# nrf24_fab.net
KiCad netlist of a schematic drawn in EAGLE
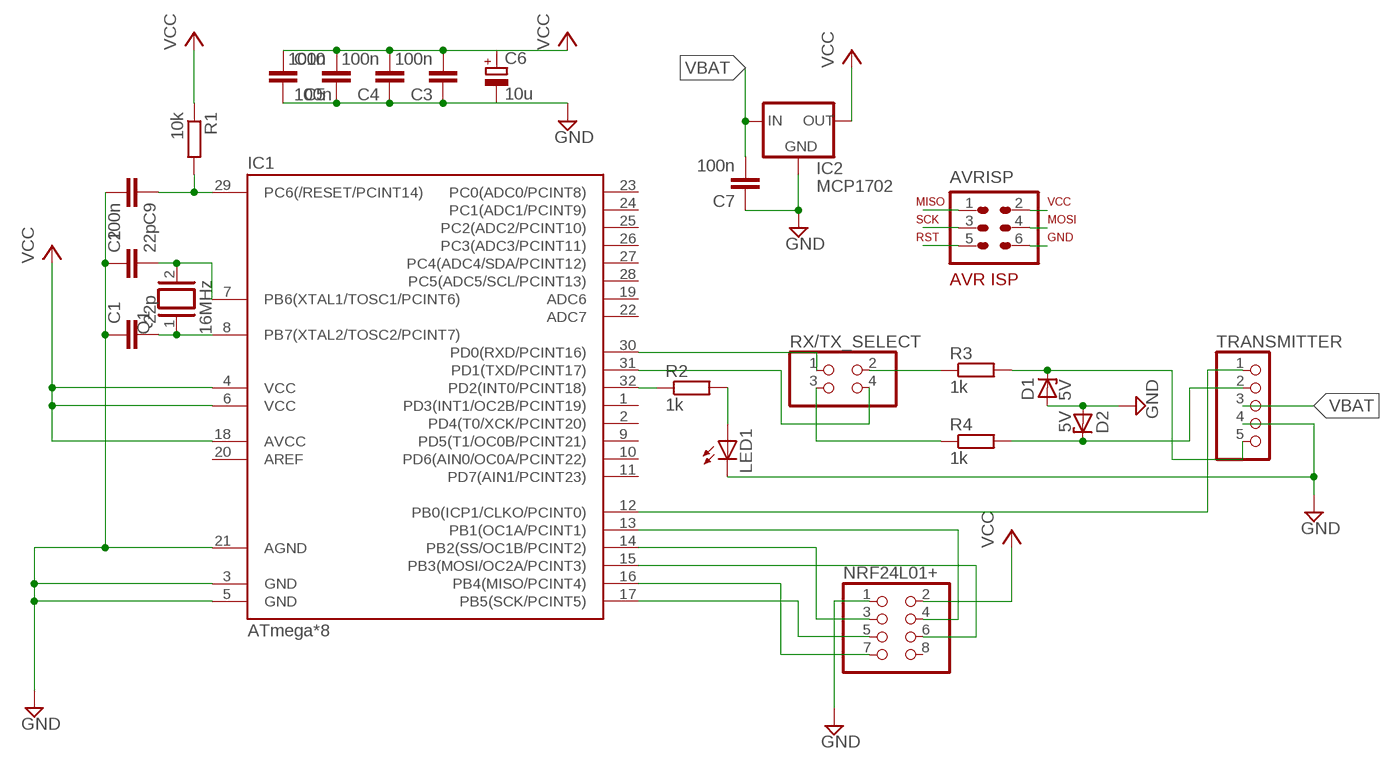
[diagram p0: schematic, sheet 1]

(export (version "E")
  (design (tool "Eeschema 10.0.6"))
  (components
    (comp (ref "AVRISP")
      (value "AVR-ISP-6VERT")
      (footprint "eagle-import:AVR-ISP-6")
      (libsource (lib "eagle-import") (part "AVR-ISP-6VERT"))
    )
    (comp (ref "C1")
      (value "22p")
      (footprint "eagle-import:C0805")
      (libsource (lib "eagle-import") (part "C-EUC0805"))
    )
    (comp (ref "C2")
      (value "22p")
      (footprint "eagle-import:C0805")
      (libsource (lib "eagle-import") (part "C-EUC0805"))
    )
    (comp (ref "C3")
      (value "100n")
      (footprint "eagle-import:C0805")
      (libsource (lib "eagle-import") (part "C-EUC0805"))
    )
    (comp (ref "C4")
      (value "100n")
      (footprint "eagle-import:C0805")
      (libsource (lib "eagle-import") (part "C-EUC0805"))
    )
    (comp (ref "C5")
      (value "100n")
      (footprint "eagle-import:C0805")
      (libsource (lib "eagle-import") (part "C-EUC0805"))
    )
    (comp (ref "C6")
      (value "10u")
      (footprint "eagle-import:E2,5-6")
      (libsource (lib "eagle-import") (part "CPOL-EUE2.5-6"))
    )
    (comp (ref "C7")
      (value "100n")
      (footprint "eagle-import:C0805")
      (libsource (lib "eagle-import") (part "C-EUC0805"))
    )
    (comp (ref "C9")
      (value "100n")
      (footprint "eagle-import:C0805")
      (libsource (lib "eagle-import") (part "C-EUC0805"))
    )
    (comp (ref "C10")
      (value "100n")
      (footprint "eagle-import:C0805")
      (libsource (lib "eagle-import") (part "C-EUC0805"))
    )
    (comp (ref "D1")
      (value "5V")
      (footprint "eagle-import:SOD80C")
      (libsource (lib "eagle-import") (part "ZENER-DIODESOD80C"))
    )
    (comp (ref "D2")
      (value "5V")
      (footprint "eagle-import:SOD80C")
      (libsource (lib "eagle-import") (part "ZENER-DIODESOD80C"))
    )
    (comp (ref "IC1")
      (value "ATmega*8")
      (footprint "eagle-import:TQFP32-08")
      (libsource (lib "eagle-import") (part "MEGA48/88/168-AU"))
    )
    (comp (ref "IC2")
      (value "MCP1702")
      (footprint "eagle-import:TO-92")
      (libsource (lib "eagle-import") (part "MCP1702"))
    )
    (comp (ref "LED1")
      (value "LEDSMT1206")
      (footprint "eagle-import:1206")
      (libsource (lib "eagle-import") (part "LEDSMT1206"))
    )
    (comp (ref "NRF24L01+")
      (value "PINHD-2X4")
      (footprint "eagle-import:2X04")
      (libsource (lib "eagle-import") (part "PINHD-2X4"))
    )
    (comp (ref "Q1")
      (value "16MHz")
      (footprint "eagle-import:QS")
      (libsource (lib "eagle-import") (part "XTAL/S"))
    )
    (comp (ref "R1")
      (value "10k")
      (footprint "eagle-import:M0805")
      (libsource (lib "eagle-import") (part "R-EU_M0805"))
    )
    (comp (ref "R2")
      (value "1k")
      (footprint "eagle-import:M0805")
      (libsource (lib "eagle-import") (part "R-EU_M0805"))
    )
    (comp (ref "R3")
      (value "1k")
      (footprint "eagle-import:M0805")
      (libsource (lib "eagle-import") (part "R-EU_M0805"))
    )
    (comp (ref "R4")
      (value "1k")
      (footprint "eagle-import:M0805")
      (libsource (lib "eagle-import") (part "R-EU_M0805"))
    )
    (comp (ref "RX/TX_SELECT")
      (value "PINHD-2X2")
      (footprint "eagle-import:2X02")
      (libsource (lib "eagle-import") (part "PINHD-2X2"))
    )
    (comp (ref "TRANSMITTER")
      (value "PINHD-1X5")
      (footprint "eagle-import:1X05")
      (libsource (lib "eagle-import") (part "PINHD-1X5"))
    )
  )
  (nets
    (net (code "1") (name "/MISO") (class "Default")
      (node (ref "AVRISP") (pin "1") (pinfunction "1_1") (pintype "passive"))
      (node (ref "IC1") (pin "16") (pinfunction "PB4(MISO/PCINT4)_16") (pintype "bidirectional"))
      (node (ref "NRF24L01+") (pin "7") (pinfunction "7_7") (pintype "passive"))
    )
    (net (code "2") (name "/MOSI") (class "Default")
      (node (ref "AVRISP") (pin "4") (pinfunction "4_4") (pintype "passive"))
      (node (ref "IC1") (pin "15") (pinfunction "PB3(MOSI/OC2A/PCINT3)_15") (pintype "bidirectional"))
      (node (ref "NRF24L01+") (pin "6") (pinfunction "6_6") (pintype "passive"))
    )
    (net (code "3") (name "/RST") (class "Default")
      (node (ref "AVRISP") (pin "5") (pinfunction "5_5") (pintype "passive"))
      (node (ref "C9") (pin "1") (pinfunction "1_1") (pintype "passive"))
      (node (ref "IC1") (pin "29") (pinfunction "PC6(/RESET/PCINT14)_29") (pintype "bidirectional"))
      (node (ref "R1") (pin "2") (pinfunction "2_2") (pintype "passive"))
    )
    (net (code "4") (name "/SCK") (class "Default")
      (node (ref "AVRISP") (pin "3") (pinfunction "3_3") (pintype "passive"))
      (node (ref "IC1") (pin "17") (pinfunction "PB5(SCK/PCINT5)_17") (pintype "bidirectional"))
      (node (ref "NRF24L01+") (pin "5") (pinfunction "5_5") (pintype "passive"))
    )
    (net (code "5") (name "GND") (class "Default")
      (node (ref "AVRISP") (pin "6") (pinfunction "6_6") (pintype "passive"))
      (node (ref "C1") (pin "1") (pinfunction "1_1") (pintype "passive"))
      (node (ref "C10") (pin "2") (pinfunction "2_2") (pintype "passive"))
      (node (ref "C2") (pin "1") (pinfunction "1_1") (pintype "passive"))
      (node (ref "C3") (pin "1") (pinfunction "1_1") (pintype "passive"))
      (node (ref "C4") (pin "1") (pinfunction "1_1") (pintype "passive"))
      (node (ref "C5") (pin "1") (pinfunction "1_1") (pintype "passive"))
      (node (ref "C6") (pin "-") (pinfunction "-_-") (pintype "passive"))
      (node (ref "C7") (pin "1") (pinfunction "1_1") (pintype "passive"))
      (node (ref "C9") (pin "2") (pinfunction "2_2") (pintype "passive"))
      (node (ref "D1") (pin "A") (pinfunction "A_A") (pintype "passive"))
      (node (ref "D2") (pin "A") (pinfunction "A_A") (pintype "passive"))
      (node (ref "IC1") (pin "21") (pinfunction "AGND_21") (pintype "power_in"))
      (node (ref "IC1") (pin "3") (pinfunction "GND_3") (pintype "power_in"))
      (node (ref "IC1") (pin "5") (pinfunction "GND_5") (pintype "power_in"))
      (node (ref "IC2") (pin "1") (pinfunction "GND_1") (pintype "power_in"))
      (node (ref "LED1") (pin "C") (pinfunction "C_C") (pintype "passive"))
      (node (ref "NRF24L01+") (pin "1") (pinfunction "1_1") (pintype "passive"))
      (node (ref "TRANSMITTER") (pin "4") (pinfunction "4_4") (pintype "passive"))
    )
    (net (code "6") (name "Net-(D1-PadC)") (class "Default")
      (node (ref "D1") (pin "C") (pinfunction "C_C") (pintype "passive"))
      (node (ref "R3") (pin "2") (pinfunction "2_2") (pintype "passive"))
      (node (ref "TRANSMITTER") (pin "5") (pinfunction "5_5") (pintype "passive"))
    )
    (net (code "7") (name "Net-(D2-PadC)") (class "Default")
      (node (ref "D2") (pin "C") (pinfunction "C_C") (pintype "passive"))
      (node (ref "R4") (pin "2") (pinfunction "2_2") (pintype "passive"))
      (node (ref "TRANSMITTER") (pin "2") (pinfunction "2_2") (pintype "passive"))
    )
    (net (code "8") (name "Net-(IC1-PB0(ICP1{slash}CLKO{slash}PCINT0))") (class "Default")
      (node (ref "IC1") (pin "12") (pinfunction "PB0(ICP1/CLKO/PCINT0)_12") (pintype "bidirectional"))
      (node (ref "TRANSMITTER") (pin "1") (pinfunction "1_1") (pintype "passive"))
    )
    (net (code "9") (name "Net-(IC1-PB1(OC1A{slash}PCINT1))") (class "Default")
      (node (ref "IC1") (pin "13") (pinfunction "PB1(OC1A/PCINT1)_13") (pintype "bidirectional"))
      (node (ref "NRF24L01+") (pin "4") (pinfunction "4_4") (pintype "passive"))
    )
    (net (code "10") (name "Net-(IC1-PB2(SS{slash}OC1B{slash}PCINT2))") (class "Default")
      (node (ref "IC1") (pin "14") (pinfunction "PB2(SS/OC1B/PCINT2)_14") (pintype "bidirectional"))
      (node (ref "NRF24L01+") (pin "3") (pinfunction "3_3") (pintype "passive"))
    )
    (net (code "11") (name "Net-(IC1-PB6(XTAL1{slash}TOSC1{slash}PCINT6))") (class "Default")
      (node (ref "C2") (pin "2") (pinfunction "2_2") (pintype "passive"))
      (node (ref "IC1") (pin "7") (pinfunction "PB6(XTAL1/TOSC1/PCINT6)_7") (pintype "bidirectional"))
      (node (ref "Q1") (pin "2") (pinfunction "2_2") (pintype "passive"))
    )
    (net (code "12") (name "Net-(IC1-PB7(XTAL2{slash}TOSC2{slash}PCINT7))") (class "Default")
      (node (ref "C1") (pin "2") (pinfunction "2_2") (pintype "passive"))
      (node (ref "IC1") (pin "8") (pinfunction "PB7(XTAL2/TOSC2/PCINT7)_8") (pintype "bidirectional"))
      (node (ref "Q1") (pin "1") (pinfunction "1_1") (pintype "passive"))
    )
    (net (code "13") (name "Net-(IC1-PD0(RXD{slash}PCINT16))") (class "Default")
      (node (ref "IC1") (pin "30") (pinfunction "PD0(RXD/PCINT16)_30") (pintype "bidirectional"))
      (node (ref "RX/TX_SELECT") (pin "1") (pinfunction "1_1") (pintype "passive"))
    )
    (net (code "14") (name "Net-(IC1-PD1(TXD{slash}PCINT17))") (class "Default")
      (node (ref "IC1") (pin "31") (pinfunction "PD1(TXD/PCINT17)_31") (pintype "bidirectional"))
      (node (ref "RX/TX_SELECT") (pin "4") (pinfunction "4_4") (pintype "passive"))
    )
    (net (code "15") (name "Net-(IC1-PD2(INT0{slash}PCINT18))") (class "Default")
      (node (ref "IC1") (pin "32") (pinfunction "PD2(INT0/PCINT18)_32") (pintype "bidirectional"))
      (node (ref "R2") (pin "1") (pinfunction "1_1") (pintype "passive"))
    )
    (net (code "16") (name "Net-(LED1-PadA)") (class "Default")
      (node (ref "LED1") (pin "A") (pinfunction "A_A") (pintype "passive"))
      (node (ref "R2") (pin "2") (pinfunction "2_2") (pintype "passive"))
    )
    (net (code "17") (name "Net-(R3-Pad1)") (class "Default")
      (node (ref "R3") (pin "1") (pinfunction "1_1") (pintype "passive"))
      (node (ref "RX/TX_SELECT") (pin "2") (pinfunction "2_2") (pintype "passive"))
    )
    (net (code "18") (name "Net-(R4-Pad1)") (class "Default")
      (node (ref "R4") (pin "1") (pinfunction "1_1") (pintype "passive"))
      (node (ref "RX/TX_SELECT") (pin "3") (pinfunction "3_3") (pintype "passive"))
    )
    (net (code "19") (name "VBAT") (class "Default")
      (node (ref "C7") (pin "2") (pinfunction "2_2") (pintype "passive"))
      (node (ref "IC2") (pin "2") (pinfunction "IN_2") (pintype "power_in"))
      (node (ref "TRANSMITTER") (pin "3") (pinfunction "3_3") (pintype "passive"))
    )
    (net (code "20") (name "VCC") (class "Default")
      (node (ref "AVRISP") (pin "2") (pinfunction "2_2") (pintype "passive"))
      (node (ref "C10") (pin "1") (pinfunction "1_1") (pintype "passive"))
      (node (ref "C3") (pin "2") (pinfunction "2_2") (pintype "passive"))
      (node (ref "C4") (pin "2") (pinfunction "2_2") (pintype "passive"))
      (node (ref "C5") (pin "2") (pinfunction "2_2") (pintype "passive"))
      (node (ref "C6") (pin "+") (pinfunction "+_+") (pintype "passive"))
      (node (ref "IC1") (pin "18") (pinfunction "AVCC_18") (pintype "passive"))
      (node (ref "IC1") (pin "4") (pinfunction "VCC_4") (pintype "power_in"))
      (node (ref "IC1") (pin "6") (pinfunction "VCC_6") (pintype "power_in"))
      (node (ref "IC2") (pin "3") (pinfunction "OUT_3") (pintype "power_in"))
      (node (ref "NRF24L01+") (pin "2") (pinfunction "2_2") (pintype "passive"))
      (node (ref "R1") (pin "1") (pinfunction "1_1") (pintype "passive"))
    )
    (net (code "21") (name "unconnected-(IC1-ADC6-Pad19)") (class "Default")
      (node (ref "IC1") (pin "19") (pinfunction "ADC6_19") (pintype "passive"))
    )
    (net (code "22") (name "unconnected-(IC1-ADC7-Pad22)") (class "Default")
      (node (ref "IC1") (pin "22") (pinfunction "ADC7_22") (pintype "passive"))
    )
    (net (code "23") (name "unconnected-(IC1-AREF-Pad20)") (class "Default")
      (node (ref "IC1") (pin "20") (pinfunction "AREF_20") (pintype "passive"))
    )
    (net (code "24") (name "unconnected-(IC1-PC0(ADC0{slash}PCINT8)-Pad23)") (class "Default")
      (node (ref "IC1") (pin "23") (pinfunction "PC0(ADC0/PCINT8)_23") (pintype "bidirectional"))
    )
    (net (code "25") (name "unconnected-(IC1-PC1(ADC1{slash}PCINT9)-Pad24)") (class "Default")
      (node (ref "IC1") (pin "24") (pinfunction "PC1(ADC1/PCINT9)_24") (pintype "bidirectional"))
    )
    (net (code "26") (name "unconnected-(IC1-PC2(ADC2{slash}PCINT10)-Pad25)") (class "Default")
      (node (ref "IC1") (pin "25") (pinfunction "PC2(ADC2/PCINT10)_25") (pintype "bidirectional"))
    )
    (net (code "27") (name "unconnected-(IC1-PC3(ADC3{slash}PCINT11)-Pad26)") (class "Default")
      (node (ref "IC1") (pin "26") (pinfunction "PC3(ADC3/PCINT11)_26") (pintype "bidirectional"))
    )
    (net (code "28") (name "unconnected-(IC1-PC4(ADC4{slash}SDA{slash}PCINT12)-Pad27)") (class "Default")
      (node (ref "IC1") (pin "27") (pinfunction "PC4(ADC4/SDA/PCINT12)_27") (pintype "bidirectional"))
    )
    (net (code "29") (name "unconnected-(IC1-PC5(ADC5{slash}SCL{slash}PCINT13)-Pad28)") (class "Default")
      (node (ref "IC1") (pin "28") (pinfunction "PC5(ADC5/SCL/PCINT13)_28") (pintype "bidirectional"))
    )
    (net (code "30") (name "unconnected-(IC1-PD3(INT1{slash}OC2B{slash}PCINT19)-Pad1)") (class "Default")
      (node (ref "IC1") (pin "1") (pinfunction "PD3(INT1/OC2B/PCINT19)_1") (pintype "bidirectional"))
    )
    (net (code "31") (name "unconnected-(IC1-PD4(T0{slash}XCK{slash}PCINT20)-Pad2)") (class "Default")
      (node (ref "IC1") (pin "2") (pinfunction "PD4(T0/XCK/PCINT20)_2") (pintype "bidirectional"))
    )
    (net (code "32") (name "unconnected-(IC1-PD5(T1{slash}OC0B{slash}PCINT21)-Pad9)") (class "Default")
      (node (ref "IC1") (pin "9") (pinfunction "PD5(T1/OC0B/PCINT21)_9") (pintype "bidirectional"))
    )
    (net (code "33") (name "unconnected-(IC1-PD6(AIN0{slash}OC0A{slash}PCINT22)-Pad10)") (class "Default")
      (node (ref "IC1") (pin "10") (pinfunction "PD6(AIN0/OC0A/PCINT22)_10") (pintype "bidirectional"))
    )
    (net (code "34") (name "unconnected-(IC1-PD7(AIN1{slash}PCINT23)-Pad11)") (class "Default")
      (node (ref "IC1") (pin "11") (pinfunction "PD7(AIN1/PCINT23)_11") (pintype "bidirectional"))
    )
    (net (code "35") (name "unconnected-(NRF24L01+-Pad8)") (class "Default")
      (node (ref "NRF24L01+") (pin "8") (pinfunction "8_8") (pintype "passive"))
    )
  )
)
